# mattduino_uno.net
KiCad netlist of a schematic drawn in EAGLE
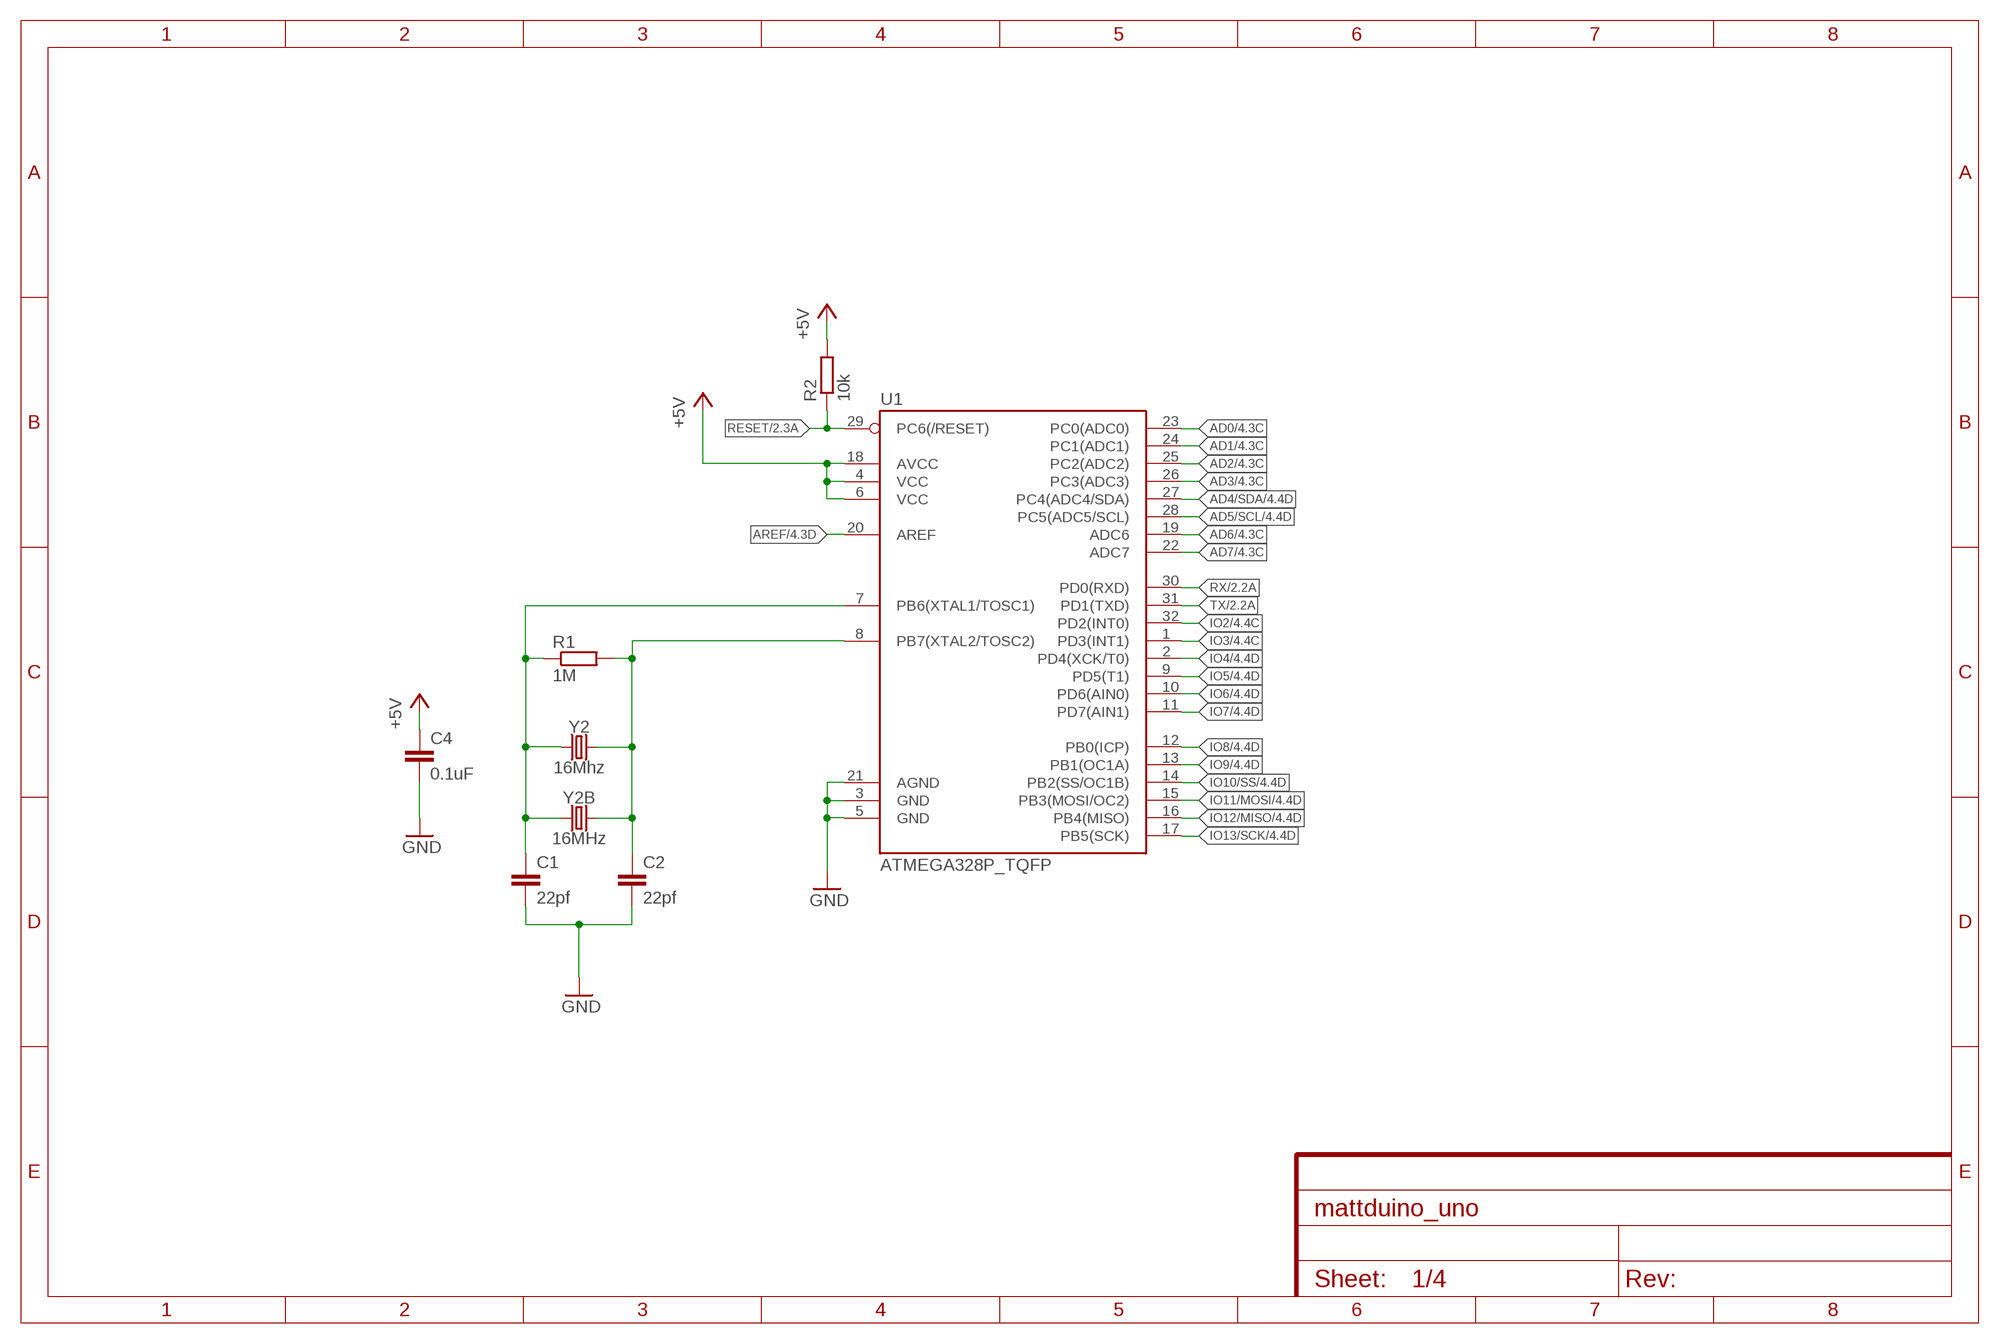
[diagram p0: schematic, sheet 1]
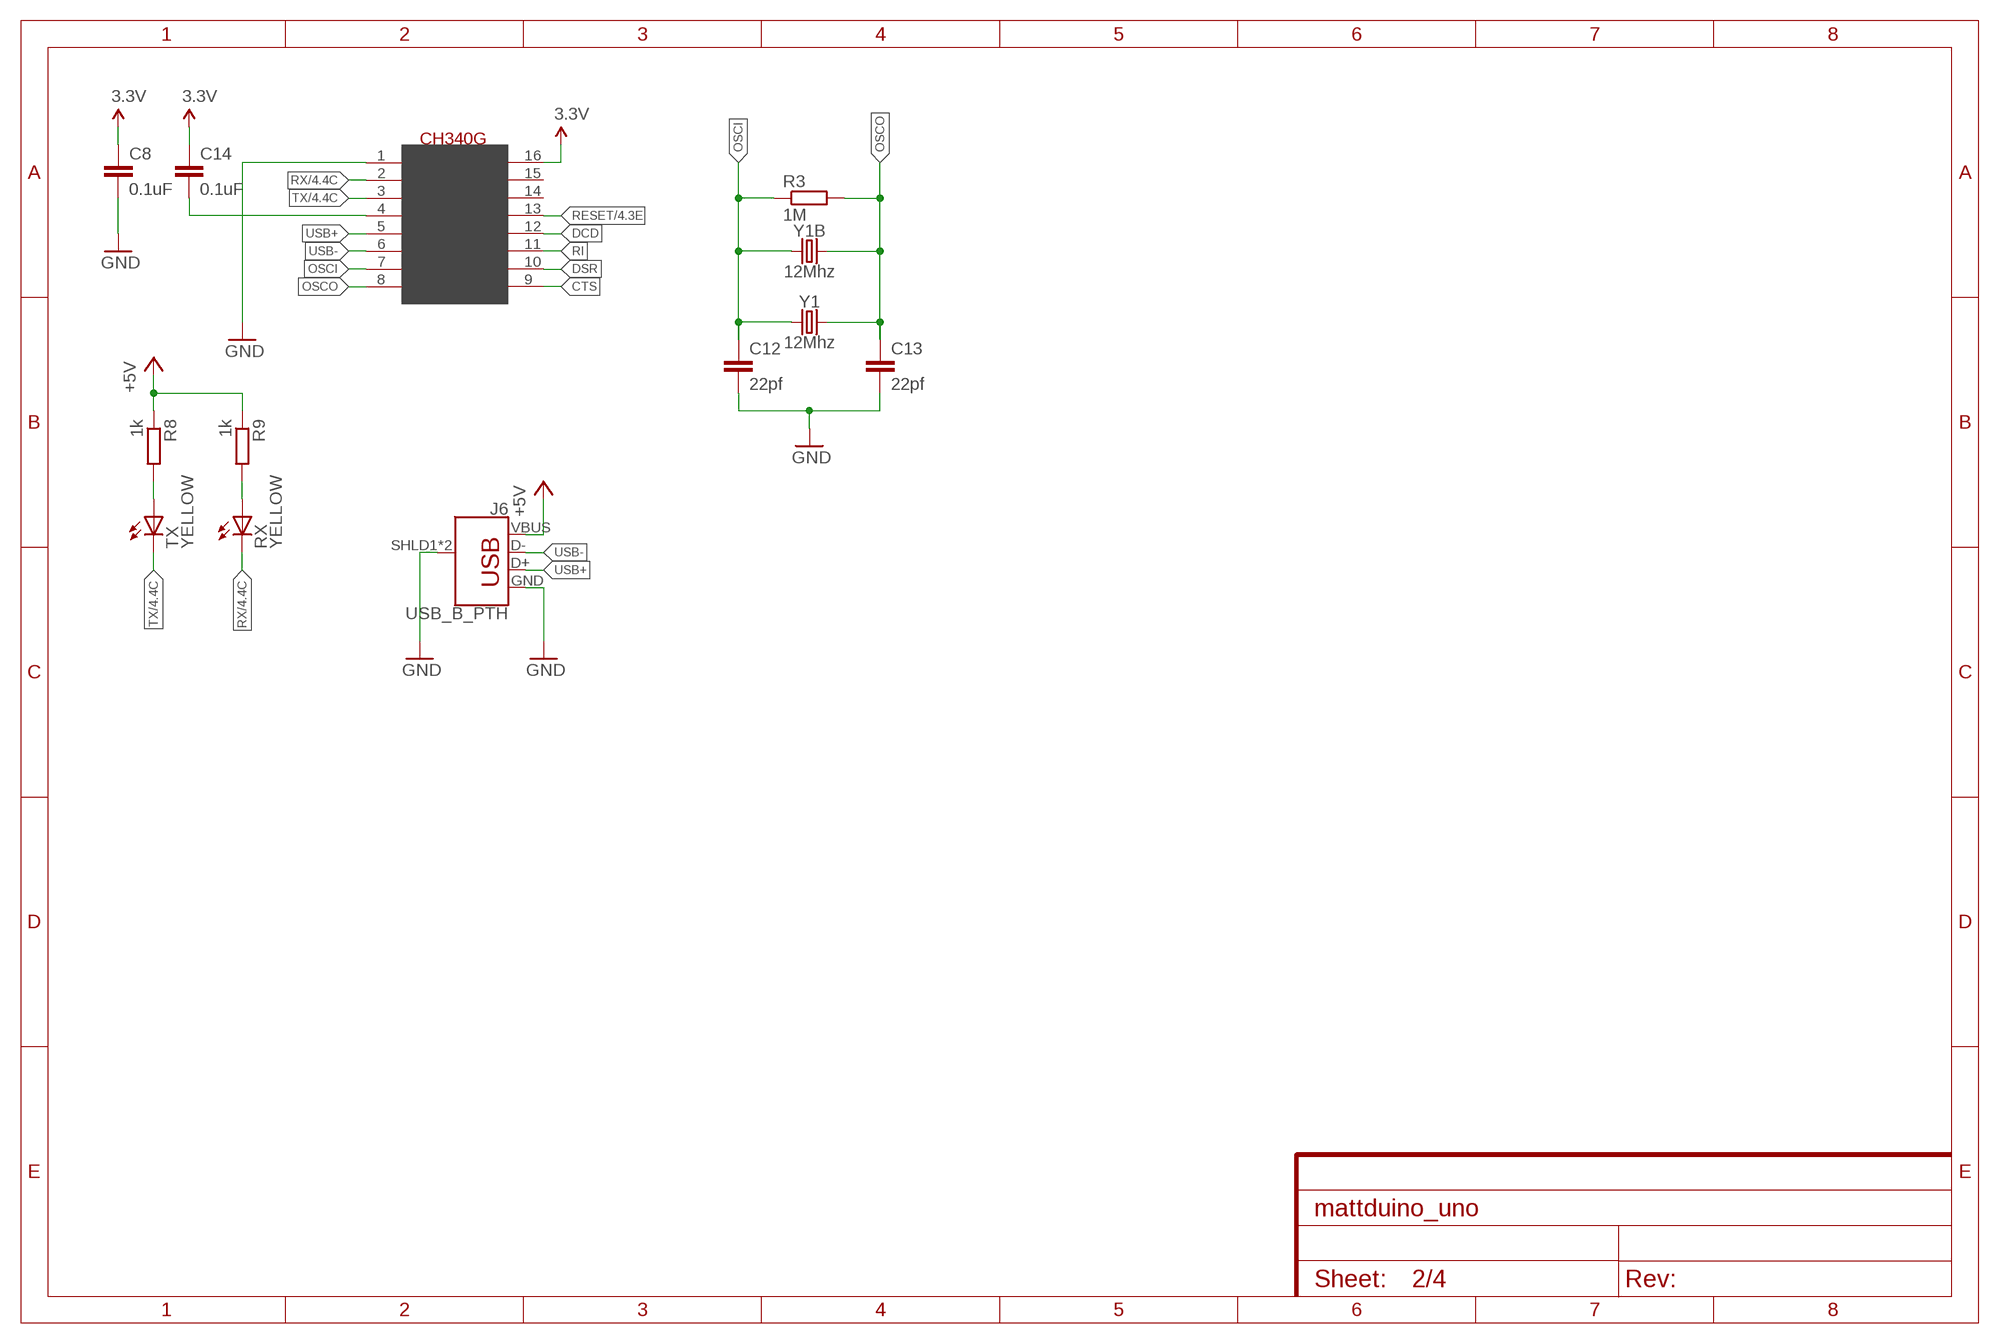
[diagram p1: schematic, sheet 2]
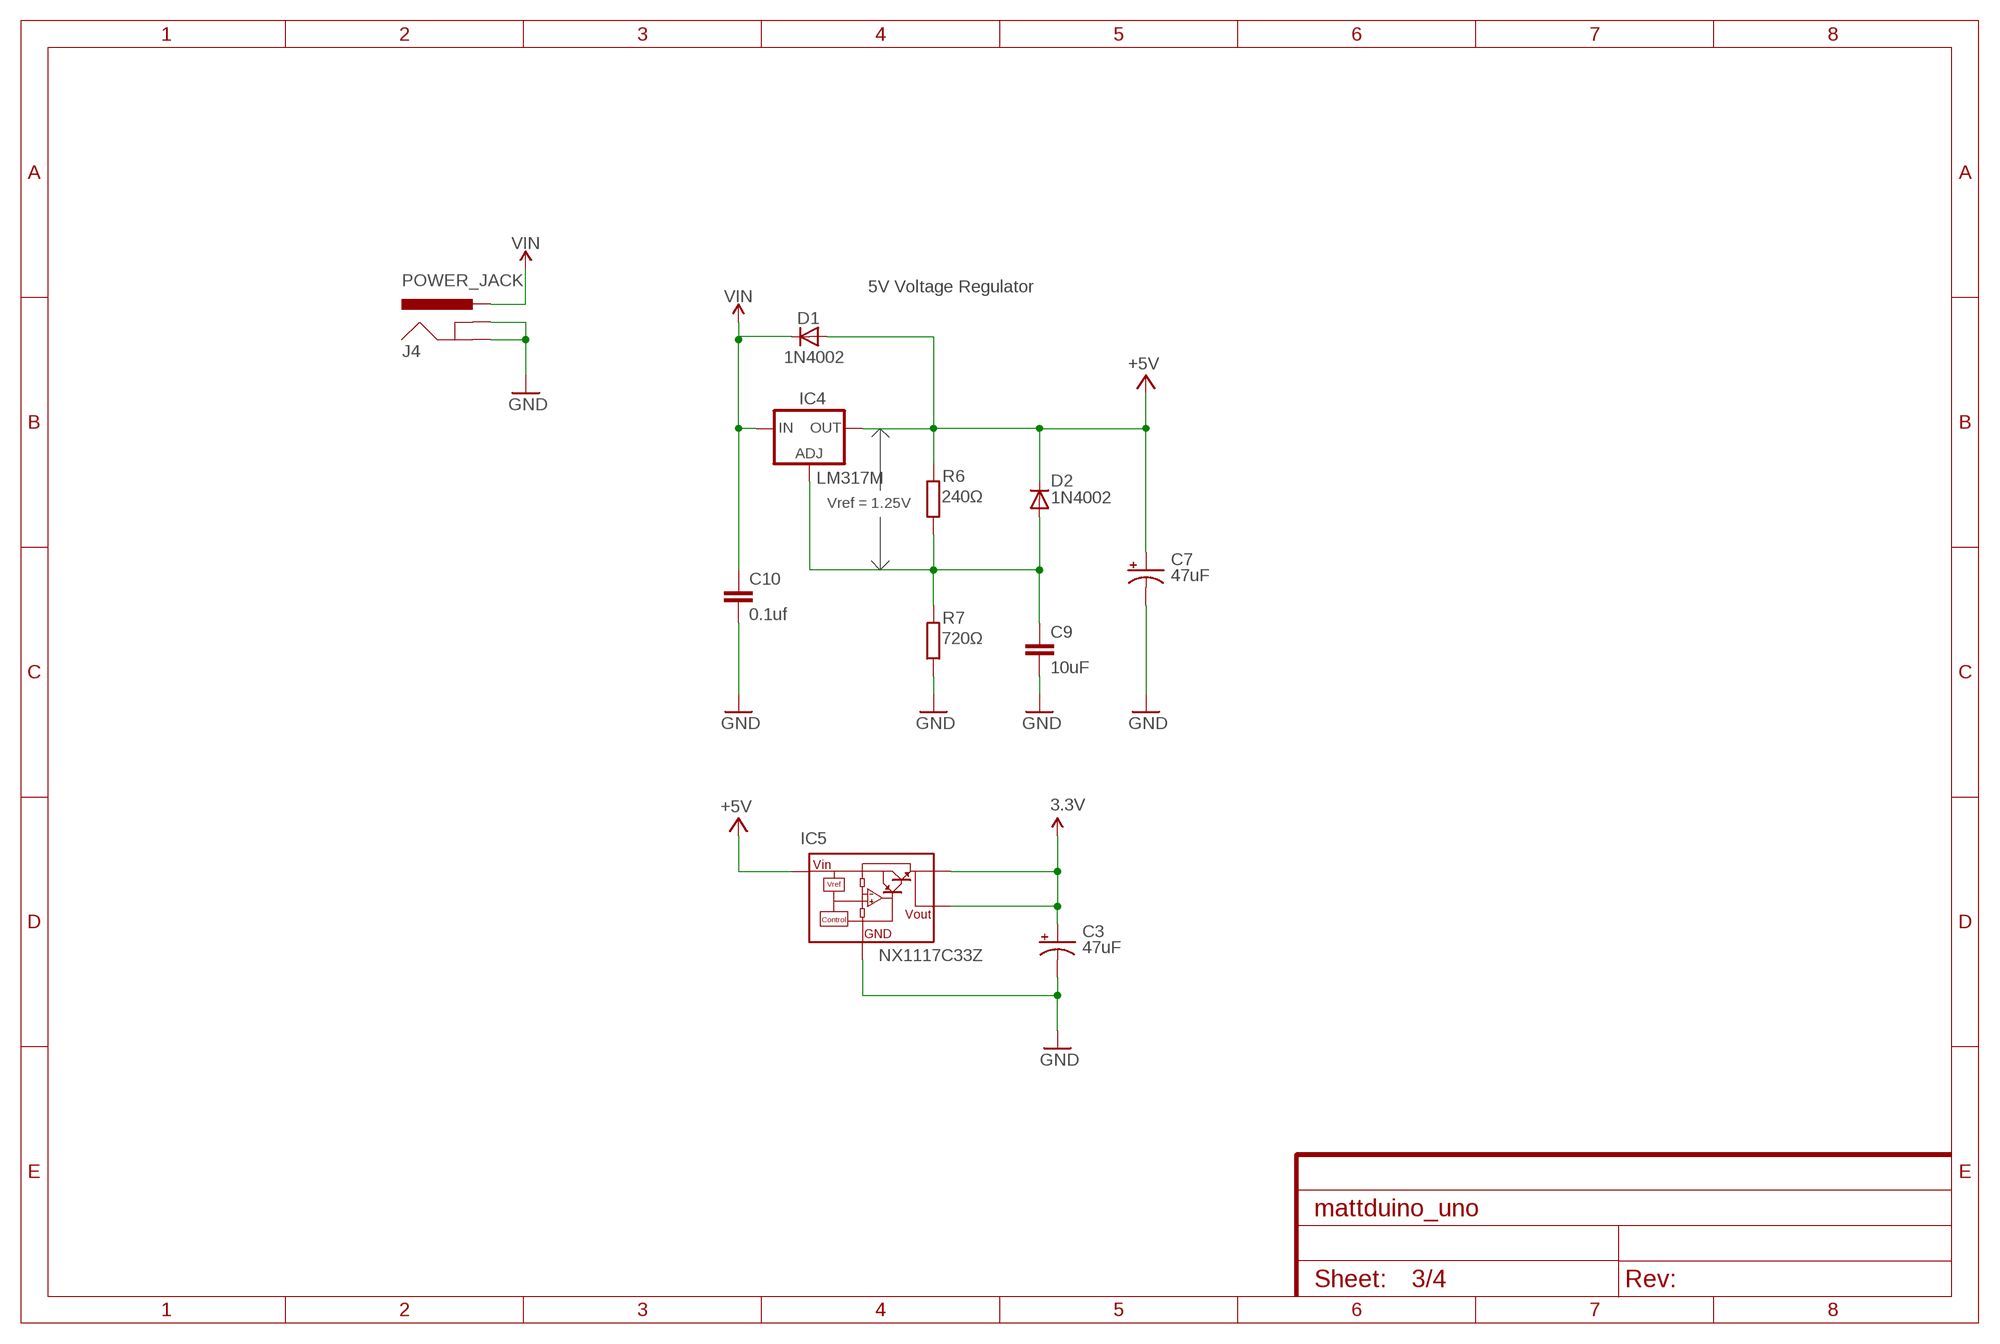
[diagram p2: schematic, sheet 3]
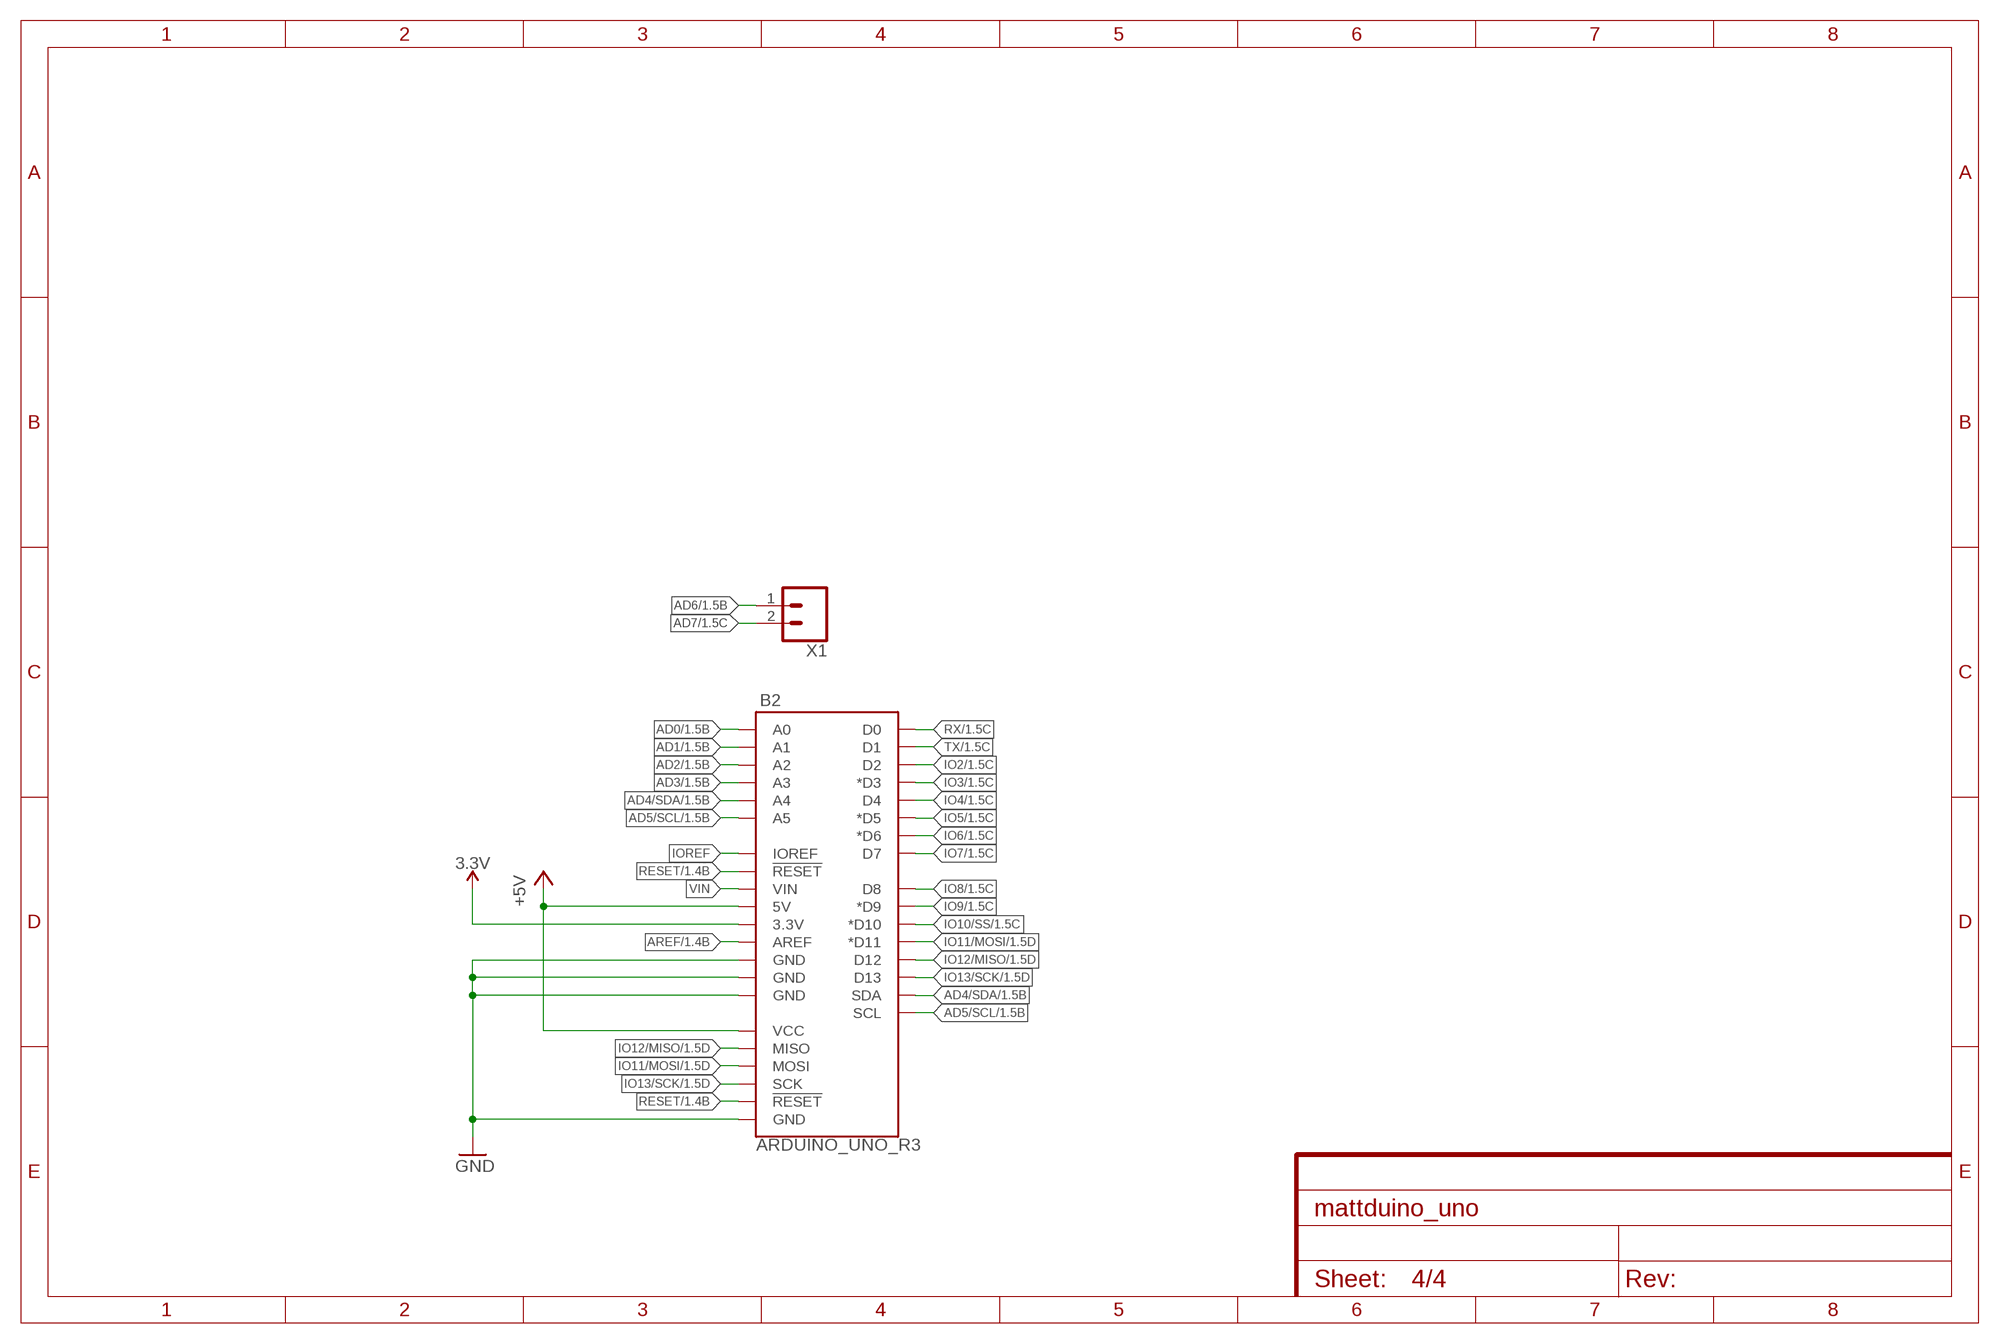
[diagram p3: schematic, sheet 4]

(export (version "E")
  (design (tool "Eeschema 10.0.6"))
  (components
    (comp (ref "B2")
      (value "ARDUINO_UNO_R3")
      (footprint "eagle-import:ARDUINO_R3")
      (libsource (lib "eagle-import") (part "ARDUINO_UNO_R3"))
    )
    (comp (ref "X1")
      (value "CONN_02")
      (footprint "eagle-import:1X02")
      (libsource (lib "eagle-import") (part "CONN_02"))
    )
    (comp (ref "C1")
      (value "22pf")
      (footprint "eagle-import:C0603")
      (libsource (lib "eagle-import") (part "rcl_334_C-EUC0603"))
    )
    (comp (ref "C2")
      (value "22pf")
      (footprint "eagle-import:C0603")
      (libsource (lib "eagle-import") (part "rcl_334_C-EUC0603"))
    )
    (comp (ref "C4")
      (value "0.1uF")
      (footprint "eagle-import:C0603")
      (libsource (lib "eagle-import") (part "rcl_334_C-EUC0603"))
    )
    (comp (ref "R1")
      (value "1M")
      (footprint "eagle-import:R0603")
      (libsource (lib "eagle-import") (part "R-EU_R0603"))
    )
    (comp (ref "R2")
      (value "10k")
      (footprint "eagle-import:R0603")
      (libsource (lib "eagle-import") (part "R-EU_R0603"))
    )
    (comp (ref "U1")
      (value "ATMEGA328P_TQFP")
      (footprint "eagle-import:TQFP32-08")
      (libsource (lib "eagle-import") (part "ATMEGA328P_TQFP"))
    )
    (comp (ref "Y2")
      (value "16Mhz")
      (footprint "eagle-import:HC49UP")
      (libsource (lib "eagle-import") (part "CRYSTAL-8MHZSMD-HC49UP"))
    )
    (comp (ref "Y2B")
      (value "16MHz")
      (footprint "eagle-import:HC49U")
      (libsource (lib "eagle-import") (part "CRYSTALPTH-HC49UV"))
    )
    (comp (ref "C3")
      (value "47uF")
      (footprint "eagle-import:PANASONIC_D")
      (libsource (lib "eagle-import") (part "47UF-POLAR-PANASONIC_D-35V-20%"))
    )
    (comp (ref "C7")
      (value "47uF")
      (footprint "eagle-import:PANASONIC_D")
      (libsource (lib "eagle-import") (part "47UF-POLAR-PANASONIC_D-35V-20%"))
    )
    (comp (ref "C9")
      (value "10uF")
      (footprint "eagle-import:C0603")
      (libsource (lib "eagle-import") (part "rcl_334_C-EUC0603"))
    )
    (comp (ref "C10")
      (value "0.1uf")
      (footprint "eagle-import:C0603")
      (libsource (lib "eagle-import") (part "rcl_334_C-EUC0603"))
    )
    (comp (ref "D1")
      (value "1N4002")
      (footprint "eagle-import:SOD-123")
      (libsource (lib "eagle-import") (part "DIODESOD-123"))
    )
    (comp (ref "D2")
      (value "1N4002")
      (footprint "eagle-import:SOD-123")
      (libsource (lib "eagle-import") (part "DIODESOD-123"))
    )
    (comp (ref "IC4")
      (value "LM317MBSTT3")
      (footprint "eagle-import:SOT223")
      (fields (field (name "PARTNUMBER") "LM317M"))
      (libsource (lib "eagle-import") (part "LM317?MBSTT3"))
    )
    (comp (ref "IC5")
      (value "NX1117C33Z")
      (footprint "eagle-import:SOT223")
      (fields (field (name "TOLERANCE") "1.25%") (field (name "VOLTAGE") "5.0V"))
      (libsource (lib "eagle-import") (part "NX1117CZ33"))
    )
    (comp (ref "J4")
      (value "POWER_JACK")
      (footprint "eagle-import:POWER_JACK_PTH")
      (libsource (lib "eagle-import") (part "POWER_JACK"))
    )
    (comp (ref "R6")
      (value "240Ω")
      (footprint "eagle-import:R0603")
      (libsource (lib "eagle-import") (part "R-EU_R0603"))
    )
    (comp (ref "R7")
      (value "720Ω")
      (footprint "eagle-import:R0603")
      (libsource (lib "eagle-import") (part "R-EU_R0603"))
    )
    (comp (ref "C8")
      (value "0.1uF")
      (footprint "eagle-import:C0603")
      (libsource (lib "eagle-import") (part "rcl_334_C-EUC0603"))
    )
    (comp (ref "C12")
      (value "22pf")
      (footprint "eagle-import:C0603")
      (libsource (lib "eagle-import") (part "rcl_334_C-EUC0603"))
    )
    (comp (ref "C13")
      (value "22pf")
      (footprint "eagle-import:C0603")
      (libsource (lib "eagle-import") (part "C-EUC0603"))
    )
    (comp (ref "C14")
      (value "0.1uF")
      (footprint "eagle-import:C0603")
      (libsource (lib "eagle-import") (part "rcl_334_C-EUC0603"))
    )
    (comp (ref "IC3")
      (value "CH340G")
      (footprint "eagle-import:SOIC16")
      (libsource (lib "eagle-import") (part "CH340G"))
    )
    (comp (ref "J6")
      (value "USB_B_PTH")
      (footprint "eagle-import:USB-B-PTH")
      (libsource (lib "eagle-import") (part "USB_B_PTH"))
    )
    (comp (ref "R3")
      (value "1M")
      (footprint "eagle-import:R0603")
      (libsource (lib "eagle-import") (part "R-EU_R0603"))
    )
    (comp (ref "R8")
      (value "1k")
      (footprint "eagle-import:R0603")
      (libsource (lib "eagle-import") (part "R-EU_R0603"))
    )
    (comp (ref "R9")
      (value "1k")
      (footprint "eagle-import:R0603")
      (libsource (lib "eagle-import") (part "R-EU_R0603"))
    )
    (comp (ref "RX")
      (value "YELLOW")
      (footprint "eagle-import:CHIP-LED0603")
      (libsource (lib "eagle-import") (part "LEDCHIP-LED0603"))
    )
    (comp (ref "TX")
      (value "YELLOW")
      (footprint "eagle-import:CHIP-LED0603")
      (libsource (lib "eagle-import") (part "LEDCHIP-LED0603"))
    )
    (comp (ref "Y1")
      (value "12Mhz")
      (footprint "eagle-import:HC49U")
      (libsource (lib "eagle-import") (part "CRYSTALPTH-HC49UV"))
    )
    (comp (ref "Y1B")
      (value "12Mhz")
      (footprint "eagle-import:HC49UP")
      (libsource (lib "eagle-import") (part "CRYSTAL-8MHZSMD-HC49UP"))
    )
  )
  (nets
    (net (code "1") (name "+5V") (class "Default")
      (node (ref "B2") (pin "5V") (pinfunction "5V_5V") (pintype "bidirectional"))
      (node (ref "B2") (pin "VCC") (pinfunction "VCC_VCC") (pintype "bidirectional"))
      (node (ref "C4") (pin "1") (pinfunction "1_1") (pintype "passive"))
      (node (ref "C7") (pin "+") (pinfunction "+_+") (pintype "passive"))
      (node (ref "D1") (pin "A") (pinfunction "A_A") (pintype "passive"))
      (node (ref "D2") (pin "C") (pinfunction "C_C") (pintype "passive"))
      (node (ref "IC4") (pin "4") (pinfunction "OUT_4") (pintype "passive"))
      (node (ref "IC5") (pin "3") (pinfunction "VIN_3") (pintype "input"))
      (node (ref "J6") (pin "VBUS") (pinfunction "VBUS_VBUS") (pintype "power_in"))
      (node (ref "R2") (pin "2") (pinfunction "2_2") (pintype "passive"))
      (node (ref "R6") (pin "2") (pinfunction "2_2") (pintype "passive"))
      (node (ref "R8") (pin "1") (pinfunction "1_1") (pintype "passive"))
      (node (ref "R9") (pin "1") (pinfunction "1_1") (pintype "passive"))
      (node (ref "U1") (pin "18") (pinfunction "AVCC_18") (pintype "bidirectional"))
      (node (ref "U1") (pin "4") (pinfunction "VCC_4") (pintype "bidirectional"))
      (node (ref "U1") (pin "6") (pinfunction "VCC_6") (pintype "bidirectional"))
    )
    (net (code "2") (name "3.3V") (class "Default")
      (node (ref "B2") (pin "3.3V") (pinfunction "3.3V_3.3V") (pintype "bidirectional"))
      (node (ref "C14") (pin "1") (pinfunction "1_1") (pintype "passive"))
      (node (ref "C3") (pin "+") (pinfunction "+_+") (pintype "passive"))
      (node (ref "C8") (pin "1") (pinfunction "1_1") (pintype "passive"))
      (node (ref "IC3") (pin "16") (pinfunction "VCC_16") (pintype "bidirectional"))
      (node (ref "IC5") (pin "2") (pinfunction "VOUT1_2") (pintype "output"))
      (node (ref "IC5") (pin "4") (pinfunction "VOUT_4") (pintype "output"))
    )
    (net (code "3") (name "AD0") (class "Default")
      (node (ref "B2") (pin "A0") (pinfunction "A0_A0") (pintype "bidirectional"))
      (node (ref "U1") (pin "23") (pinfunction "PC0(ADC0)_23") (pintype "bidirectional"))
    )
    (net (code "4") (name "AD1") (class "Default")
      (node (ref "B2") (pin "A1") (pinfunction "A1_A1") (pintype "bidirectional"))
      (node (ref "U1") (pin "24") (pinfunction "PC1(ADC1)_24") (pintype "bidirectional"))
    )
    (net (code "5") (name "AD2") (class "Default")
      (node (ref "B2") (pin "A2") (pinfunction "A2_A2") (pintype "bidirectional"))
      (node (ref "U1") (pin "25") (pinfunction "PC2(ADC2)_25") (pintype "bidirectional"))
    )
    (net (code "6") (name "AD3") (class "Default")
      (node (ref "B2") (pin "A3") (pinfunction "A3_A3") (pintype "bidirectional"))
      (node (ref "U1") (pin "26") (pinfunction "PC3(ADC3)_26") (pintype "bidirectional"))
    )
    (net (code "7") (name "AD4{slash}SDA") (class "Default")
      (node (ref "B2") (pin "A4") (pinfunction "A4_A4") (pintype "bidirectional"))
      (node (ref "B2") (pin "SDA") (pinfunction "SDA_SDA") (pintype "bidirectional"))
      (node (ref "U1") (pin "27") (pinfunction "PC4(ADC4/SDA)_27") (pintype "bidirectional"))
    )
    (net (code "8") (name "AD5{slash}SCL") (class "Default")
      (node (ref "B2") (pin "A5") (pinfunction "A5_A5") (pintype "bidirectional"))
      (node (ref "B2") (pin "SCL") (pinfunction "SCL_SCL") (pintype "bidirectional"))
      (node (ref "U1") (pin "28") (pinfunction "PC5(ADC5/SCL)_28") (pintype "bidirectional"))
    )
    (net (code "9") (name "AD6") (class "Default")
      (node (ref "U1") (pin "19") (pinfunction "ADC6_19") (pintype "bidirectional"))
      (node (ref "X1") (pin "1") (pinfunction "1_1") (pintype "passive"))
    )
    (net (code "10") (name "AD7") (class "Default")
      (node (ref "U1") (pin "22") (pinfunction "ADC7_22") (pintype "bidirectional"))
      (node (ref "X1") (pin "2") (pinfunction "2_2") (pintype "passive"))
    )
    (net (code "11") (name "AREF") (class "Default")
      (node (ref "B2") (pin "AREF") (pinfunction "AREF_AREF") (pintype "bidirectional"))
      (node (ref "U1") (pin "20") (pinfunction "AREF_20") (pintype "bidirectional"))
    )
    (net (code "12") (name "CTS") (class "Default")
      (node (ref "IC3") (pin "9") (pinfunction "CTS_9") (pintype "bidirectional"))
    )
    (net (code "13") (name "DCD") (class "Default")
      (node (ref "IC3") (pin "12") (pinfunction "DCD_12") (pintype "bidirectional"))
    )
    (net (code "14") (name "DSR") (class "Default")
      (node (ref "IC3") (pin "10") (pinfunction "DSR_10") (pintype "bidirectional"))
    )
    (net (code "15") (name "GND") (class "Default")
      (node (ref "B2") (pin "GND@1") (pinfunction "GND_GND@1") (pintype "bidirectional"))
      (node (ref "B2") (pin "GND@2") (pinfunction "GND_GND@2") (pintype "bidirectional"))
      (node (ref "B2") (pin "GND@3") (pinfunction "GND_GND@3") (pintype "bidirectional"))
      (node (ref "B2") (pin "GND@4") (pinfunction "GND_GND@4") (pintype "bidirectional"))
      (node (ref "C1") (pin "2") (pinfunction "2_2") (pintype "passive"))
      (node (ref "C10") (pin "2") (pinfunction "2_2") (pintype "passive"))
      (node (ref "C12") (pin "2") (pinfunction "2_2") (pintype "passive"))
      (node (ref "C13") (pin "2") (pinfunction "2_2") (pintype "passive"))
      (node (ref "C2") (pin "2") (pinfunction "2_2") (pintype "passive"))
      (node (ref "C3") (pin "-") (pinfunction "-_-") (pintype "passive"))
      (node (ref "C4") (pin "2") (pinfunction "2_2") (pintype "passive"))
      (node (ref "C7") (pin "-") (pinfunction "-_-") (pintype "passive"))
      (node (ref "C8") (pin "2") (pinfunction "2_2") (pintype "passive"))
      (node (ref "C9") (pin "2") (pinfunction "2_2") (pintype "passive"))
      (node (ref "IC3") (pin "1") (pinfunction "GND_1") (pintype "bidirectional"))
      (node (ref "IC5") (pin "1") (pinfunction "GND_1") (pintype "passive"))
      (node (ref "J4") (pin "GND") (pinfunction "GND_GND") (pintype "bidirectional"))
      (node (ref "J4") (pin "GNDBREAK") (pinfunction "GNDBREAK_GNDBREAK") (pintype "bidirectional"))
      (node (ref "J6") (pin "GND") (pinfunction "GND_GND") (pintype "power_in"))
      (node (ref "J6") (pin "SHLD1") (pinfunction "SHIELD_SHLD1") (pintype "bidirectional"))
      (node (ref "J6") (pin "SHLD2") (pinfunction "SHIELD_SHLD2") (pintype "bidirectional"))
      (node (ref "R7") (pin "1") (pinfunction "1_1") (pintype "passive"))
      (node (ref "U1") (pin "21") (pinfunction "AGND_21") (pintype "bidirectional"))
      (node (ref "U1") (pin "3") (pinfunction "GND_3") (pintype "bidirectional"))
      (node (ref "U1") (pin "5") (pinfunction "GND_5") (pintype "bidirectional"))
    )
    (net (code "16") (name "IO2") (class "Default")
      (node (ref "B2") (pin "D2") (pinfunction "D2_D2") (pintype "bidirectional"))
      (node (ref "U1") (pin "32") (pinfunction "PD2(INT0)_32") (pintype "bidirectional"))
    )
    (net (code "17") (name "IO3") (class "Default")
      (node (ref "B2") (pin "D3") (pinfunction "*D3_D3") (pintype "bidirectional"))
      (node (ref "U1") (pin "1") (pinfunction "PD3(INT1)_1") (pintype "bidirectional"))
    )
    (net (code "18") (name "IO4") (class "Default")
      (node (ref "B2") (pin "D4") (pinfunction "D4_D4") (pintype "bidirectional"))
      (node (ref "U1") (pin "2") (pinfunction "PD4(XCK/T0)_2") (pintype "bidirectional"))
    )
    (net (code "19") (name "IO5") (class "Default")
      (node (ref "B2") (pin "D5") (pinfunction "*D5_D5") (pintype "bidirectional"))
      (node (ref "U1") (pin "9") (pinfunction "PD5(T1)_9") (pintype "bidirectional"))
    )
    (net (code "20") (name "IO6") (class "Default")
      (node (ref "B2") (pin "D6") (pinfunction "*D6_D6") (pintype "bidirectional"))
      (node (ref "U1") (pin "10") (pinfunction "PD6(AIN0)_10") (pintype "bidirectional"))
    )
    (net (code "21") (name "IO7") (class "Default")
      (node (ref "B2") (pin "D7") (pinfunction "D7_D7") (pintype "bidirectional"))
      (node (ref "U1") (pin "11") (pinfunction "PD7(AIN1)_11") (pintype "bidirectional"))
    )
    (net (code "22") (name "IO8") (class "Default")
      (node (ref "B2") (pin "D8") (pinfunction "D8_D8") (pintype "bidirectional"))
      (node (ref "U1") (pin "12") (pinfunction "PB0(ICP)_12") (pintype "bidirectional"))
    )
    (net (code "23") (name "IO9") (class "Default")
      (node (ref "B2") (pin "D9") (pinfunction "*D9_D9") (pintype "bidirectional"))
      (node (ref "U1") (pin "13") (pinfunction "PB1(OC1A)_13") (pintype "bidirectional"))
    )
    (net (code "24") (name "IO10{slash}SS") (class "Default")
      (node (ref "B2") (pin "D10") (pinfunction "*D10_D10") (pintype "bidirectional"))
      (node (ref "U1") (pin "14") (pinfunction "PB2(SS/OC1B)_14") (pintype "bidirectional"))
    )
    (net (code "25") (name "IO11{slash}MOSI") (class "Default")
      (node (ref "B2") (pin "D11") (pinfunction "*D11_D11") (pintype "bidirectional"))
      (node (ref "B2") (pin "MOSI") (pinfunction "MOSI_MOSI") (pintype "bidirectional"))
      (node (ref "U1") (pin "15") (pinfunction "PB3(MOSI/OC2)_15") (pintype "bidirectional"))
    )
    (net (code "26") (name "IO12{slash}MISO") (class "Default")
      (node (ref "B2") (pin "D12") (pinfunction "D12_D12") (pintype "bidirectional"))
      (node (ref "B2") (pin "MISO") (pinfunction "MISO_MISO") (pintype "bidirectional"))
      (node (ref "U1") (pin "16") (pinfunction "PB4(MISO)_16") (pintype "bidirectional"))
    )
    (net (code "27") (name "IO13{slash}SCK") (class "Default")
      (node (ref "B2") (pin "D13") (pinfunction "D13_D13") (pintype "bidirectional"))
      (node (ref "B2") (pin "SCK") (pinfunction "SCK_SCK") (pintype "bidirectional"))
      (node (ref "U1") (pin "17") (pinfunction "PB5(SCK)_17") (pintype "bidirectional"))
    )
    (net (code "28") (name "IOREF") (class "Default")
      (node (ref "B2") (pin "IOREF") (pinfunction "IOREF_IOREF") (pintype "bidirectional"))
    )
    (net (code "29") (name "Net-(IC3-V3)") (class "Default")
      (node (ref "C14") (pin "2") (pinfunction "2_2") (pintype "passive"))
      (node (ref "IC3") (pin "4") (pinfunction "V3_4") (pintype "bidirectional"))
    )
    (net (code "30") (name "Net-(IC4-ADJ)") (class "Default")
      (node (ref "C9") (pin "1") (pinfunction "1_1") (pintype "passive"))
      (node (ref "D2") (pin "A") (pinfunction "A_A") (pintype "passive"))
      (node (ref "IC4") (pin "1") (pinfunction "ADJ_1") (pintype "input"))
      (node (ref "R6") (pin "1") (pinfunction "1_1") (pintype "passive"))
      (node (ref "R7") (pin "2") (pinfunction "2_2") (pintype "passive"))
    )
    (net (code "31") (name "Net-(R8-Pad2)") (class "Default")
      (node (ref "R8") (pin "2") (pinfunction "2_2") (pintype "passive"))
      (node (ref "TX") (pin "A") (pinfunction "A_A") (pintype "passive"))
    )
    (net (code "32") (name "Net-(R9-Pad2)") (class "Default")
      (node (ref "R9") (pin "2") (pinfunction "2_2") (pintype "passive"))
      (node (ref "RX") (pin "A") (pinfunction "A_A") (pintype "passive"))
    )
    (net (code "33") (name "Net-(U1-PB6(XTAL1{slash}TOSC1))") (class "Default")
      (node (ref "C1") (pin "1") (pinfunction "1_1") (pintype "passive"))
      (node (ref "R1") (pin "1") (pinfunction "1_1") (pintype "passive"))
      (node (ref "U1") (pin "7") (pinfunction "PB6(XTAL1/TOSC1)_7") (pintype "bidirectional"))
      (node (ref "Y2") (pin "1") (pinfunction "1_1") (pintype "passive"))
      (node (ref "Y2B") (pin "1") (pinfunction "1_1") (pintype "passive"))
    )
    (net (code "34") (name "Net-(U1-PB7(XTAL2{slash}TOSC2))") (class "Default")
      (node (ref "C2") (pin "1") (pinfunction "1_1") (pintype "passive"))
      (node (ref "R1") (pin "2") (pinfunction "2_2") (pintype "passive"))
      (node (ref "U1") (pin "8") (pinfunction "PB7(XTAL2/TOSC2)_8") (pintype "bidirectional"))
      (node (ref "Y2") (pin "2") (pinfunction "2_2") (pintype "passive"))
      (node (ref "Y2B") (pin "2") (pinfunction "2_2") (pintype "passive"))
    )
    (net (code "35") (name "OSCI") (class "Default")
      (node (ref "C12") (pin "1") (pinfunction "1_1") (pintype "passive"))
      (node (ref "IC3") (pin "7") (pinfunction "XI_7") (pintype "bidirectional"))
      (node (ref "R3") (pin "1") (pinfunction "1_1") (pintype "passive"))
      (node (ref "Y1") (pin "1") (pinfunction "1_1") (pintype "passive"))
      (node (ref "Y1B") (pin "1") (pinfunction "1_1") (pintype "passive"))
    )
    (net (code "36") (name "OSCO") (class "Default")
      (node (ref "C13") (pin "1") (pinfunction "1_1") (pintype "passive"))
      (node (ref "IC3") (pin "8") (pinfunction "XO_8") (pintype "bidirectional"))
      (node (ref "R3") (pin "2") (pinfunction "2_2") (pintype "passive"))
      (node (ref "Y1") (pin "2") (pinfunction "2_2") (pintype "passive"))
      (node (ref "Y1B") (pin "2") (pinfunction "2_2") (pintype "passive"))
    )
    (net (code "37") (name "RESET") (class "Default")
      (node (ref "B2") (pin "RESET@1") (pinfunction "~{RESET}_RESET@1") (pintype "bidirectional"))
      (node (ref "B2") (pin "RESET@2") (pinfunction "~{RESET}_RESET@2") (pintype "bidirectional"))
      (node (ref "IC3") (pin "13") (pinfunction "DTR_13") (pintype "bidirectional"))
      (node (ref "R2") (pin "1") (pinfunction "1_1") (pintype "passive"))
      (node (ref "U1") (pin "29") (pinfunction "PC6(/RESET)_29") (pintype "bidirectional"))
    )
    (net (code "38") (name "RI") (class "Default")
      (node (ref "IC3") (pin "11") (pinfunction "RI_11") (pintype "bidirectional"))
    )
    (net (code "39") (name "RX") (class "Default")
      (node (ref "B2") (pin "D0") (pinfunction "D0_D0") (pintype "bidirectional"))
      (node (ref "IC3") (pin "2") (pinfunction "TX_2") (pintype "bidirectional"))
      (node (ref "RX") (pin "C") (pinfunction "C_C") (pintype "passive"))
      (node (ref "U1") (pin "30") (pinfunction "PD0(RXD)_30") (pintype "bidirectional"))
    )
    (net (code "40") (name "TX") (class "Default")
      (node (ref "B2") (pin "D1") (pinfunction "D1_D1") (pintype "bidirectional"))
      (node (ref "IC3") (pin "3") (pinfunction "RX_3") (pintype "bidirectional"))
      (node (ref "TX") (pin "C") (pinfunction "C_C") (pintype "passive"))
      (node (ref "U1") (pin "31") (pinfunction "PD1(TXD)_31") (pintype "bidirectional"))
    )
    (net (code "41") (name "USB+") (class "Default")
      (node (ref "IC3") (pin "5") (pinfunction "D+_5") (pintype "bidirectional"))
      (node (ref "J6") (pin "D+") (pinfunction "D+_D+") (pintype "bidirectional"))
    )
    (net (code "42") (name "USB-") (class "Default")
      (node (ref "IC3") (pin "6") (pinfunction "D-_6") (pintype "bidirectional"))
      (node (ref "J6") (pin "D-") (pinfunction "D-_D-") (pintype "bidirectional"))
    )
    (net (code "43") (name "VIN") (class "Default")
      (node (ref "B2") (pin "VIN") (pinfunction "VIN_VIN") (pintype "bidirectional"))
      (node (ref "C10") (pin "1") (pinfunction "1_1") (pintype "passive"))
      (node (ref "D1") (pin "C") (pinfunction "C_C") (pintype "passive"))
      (node (ref "IC4") (pin "3") (pinfunction "IN_3") (pintype "input"))
      (node (ref "J4") (pin "PWR") (pinfunction "PWR_PWR") (pintype "bidirectional"))
    )
    (net (code "44") (name "unconnected-(IC3-RS232-Pad15)") (class "Default")
      (node (ref "IC3") (pin "15") (pinfunction "RS232_15") (pintype "bidirectional"))
    )
    (net (code "45") (name "unconnected-(IC3-RTS-Pad14)") (class "Default")
      (node (ref "IC3") (pin "14") (pinfunction "RTS_14") (pintype "bidirectional"))
    )
  )
)
